# emonthKsm_1.net
KiCad netlist of a schematic drawn in EAGLE
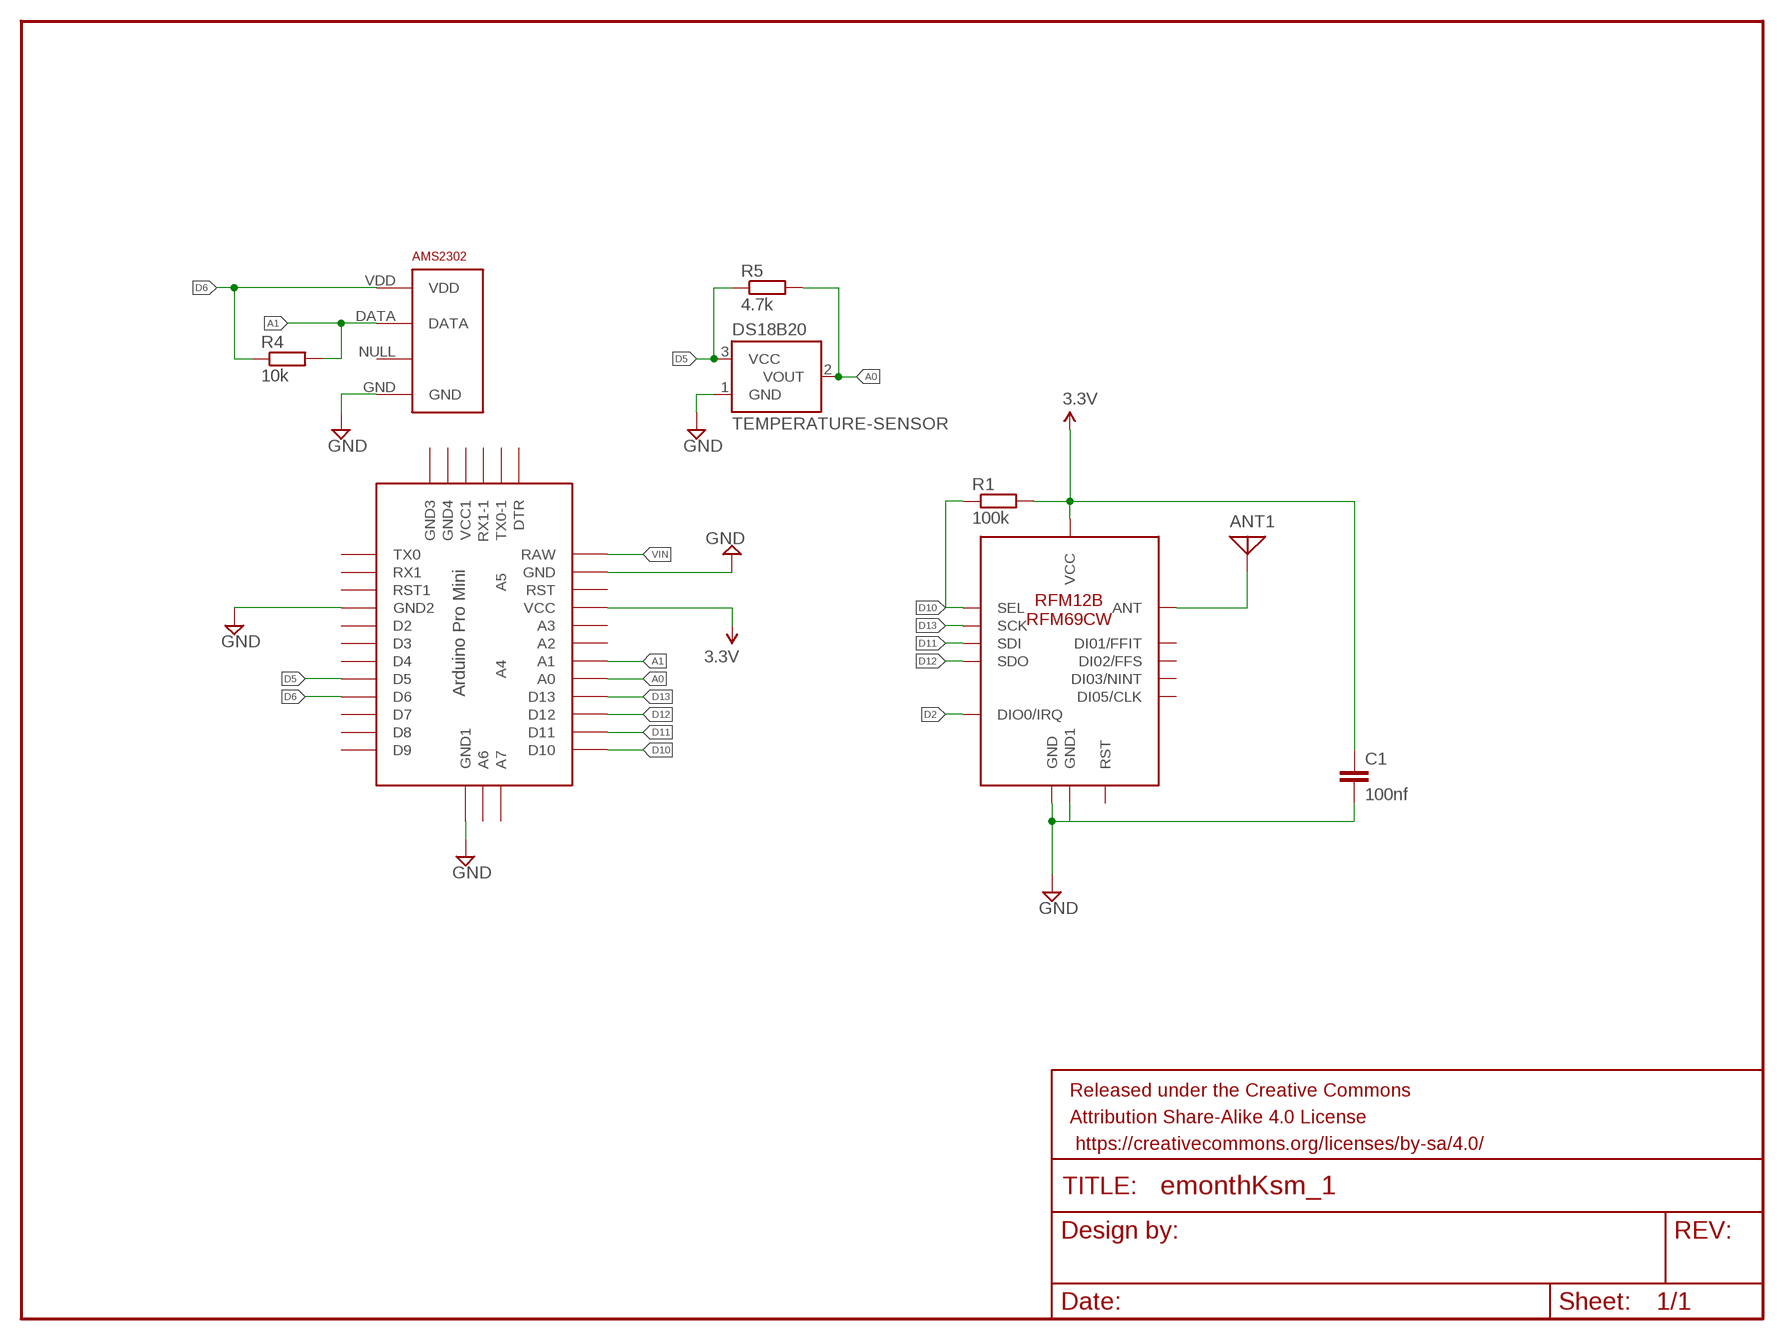
[diagram p0: schematic, sheet 1]

(export (version "E")
  (design (tool "Eeschema 10.0.6"))
  (components
    (comp (ref "AMS2302")
      (value "RHT03_DHT-22_AM2302")
      (footprint "eagle-import:RHT03_DHT-22")
      (libsource (lib "eagle-import") (part "RHT03_DHT-22_AM2302"))
    )
    (comp (ref "ANT1")
      (value "ANTENNA")
      (footprint "eagle-import:PAD-01")
      (libsource (lib "eagle-import") (part "ANTENNA"))
    )
    (comp (ref "ARDUINO")
      (value "ABK-PRO-MINI")
      (footprint "eagle-import:ABK-PRO-MINI")
      (libsource (lib "eagle-import") (part "ABK-PRO-MINI"))
    )
    (comp (ref "C1")
      (value "100nf")
      (footprint "eagle-import:C050-050X075")
      (libsource (lib "eagle-import") (part "C-EU050-050X075"))
    )
    (comp (ref "DS18B20")
      (value "TEMPERATURE-SENSOR")
      (footprint "eagle-import:TO-92")
      (libsource (lib "eagle-import") (part "TEMPERATURE-SENSOR"))
    )
    (comp (ref "FRAME1")
      (value "FRAME-LETTERNO_PACKAGE")
      (footprint "eagle-import:DUMMY")
      (fields (field (name "DESIGNER") "Nobody"))
      (libsource (lib "eagle-import") (part "FRAME-LETTERNO_PACKAGE"))
    )
    (comp (ref "R1")
      (value "100k")
      (footprint "eagle-import:0204_7")
      (libsource (lib "eagle-import") (part "R-EU_0204/7"))
    )
    (comp (ref "R4")
      (value "10k")
      (footprint "eagle-import:0204_7")
      (libsource (lib "eagle-import") (part "R-EU_0204/7"))
    )
    (comp (ref "R5")
      (value "4.7k")
      (footprint "eagle-import:0204_7")
      (libsource (lib "eagle-import") (part "R-EU_0204/7"))
    )
    (comp (ref "RFM69")
      (value "RFM12B/69CW")
      (footprint "eagle-import:RFM12B_69CW")
      (libsource (lib "eagle-import") (part "RFM12B/69CW"))
    )
  )
  (nets
    (net (code "1") (name "3.3V") (class "Default")
      (node (ref "ARDUINO") (pin "VCC") (pinfunction "VCC_VCC") (pintype "bidirectional"))
      (node (ref "C1") (pin "1") (pinfunction "1_1") (pintype "passive"))
      (node (ref "R1") (pin "2") (pinfunction "2_2") (pintype "passive"))
      (node (ref "RFM69") (pin "VDD") (pinfunction "VCC_VDD") (pintype "power_in"))
    )
    (net (code "2") (name "A0") (class "Default")
      (node (ref "ARDUINO") (pin "A0") (pinfunction "A0_A0") (pintype "bidirectional"))
      (node (ref "DS18B20") (pin "2") (pinfunction "VOUT_2") (pintype "bidirectional"))
      (node (ref "R5") (pin "2") (pinfunction "2_2") (pintype "passive"))
    )
    (net (code "3") (name "A1") (class "Default")
      (node (ref "AMS2302") (pin "DATA") (pinfunction "DATA_DATA") (pintype "bidirectional"))
      (node (ref "ARDUINO") (pin "A1") (pinfunction "A1_A1") (pintype "bidirectional"))
      (node (ref "R4") (pin "2") (pinfunction "2_2") (pintype "passive"))
    )
    (net (code "4") (name "D2") (class "Default")
      (node (ref "RFM69") (pin "IRQ") (pinfunction "DIO0/IRQ_IRQ") (pintype "open_collector"))
    )
    (net (code "5") (name "D5") (class "Default")
      (node (ref "ARDUINO") (pin "D5") (pinfunction "D5_D5") (pintype "bidirectional"))
      (node (ref "DS18B20") (pin "3") (pinfunction "VCC_3") (pintype "bidirectional"))
      (node (ref "R5") (pin "1") (pinfunction "1_1") (pintype "passive"))
    )
    (net (code "6") (name "D6") (class "Default")
      (node (ref "AMS2302") (pin "VDD") (pinfunction "VDD_VDD") (pintype "power_in"))
      (node (ref "ARDUINO") (pin "D6") (pinfunction "D6_D6") (pintype "bidirectional"))
      (node (ref "R4") (pin "1") (pinfunction "1_1") (pintype "passive"))
    )
    (net (code "7") (name "D10") (class "Default")
      (node (ref "ARDUINO") (pin "D10") (pinfunction "D10_D10") (pintype "bidirectional"))
      (node (ref "R1") (pin "1") (pinfunction "1_1") (pintype "passive"))
      (node (ref "RFM69") (pin "SEL") (pinfunction "SEL_SEL") (pintype "input"))
    )
    (net (code "8") (name "D11") (class "Default")
      (node (ref "ARDUINO") (pin "D11") (pinfunction "D11_D11") (pintype "bidirectional"))
      (node (ref "RFM69") (pin "SDI") (pinfunction "SDI_SDI") (pintype "input"))
    )
    (net (code "9") (name "D12") (class "Default")
      (node (ref "ARDUINO") (pin "D12") (pinfunction "D12_D12") (pintype "bidirectional"))
      (node (ref "RFM69") (pin "SDO") (pinfunction "SDO_SDO") (pintype "output"))
    )
    (net (code "10") (name "D13") (class "Default")
      (node (ref "ARDUINO") (pin "D13") (pinfunction "D13_D13") (pintype "bidirectional"))
      (node (ref "RFM69") (pin "SCK") (pinfunction "SCK_SCK") (pintype "input"))
    )
    (net (code "11") (name "GND") (class "Default")
      (node (ref "AMS2302") (pin "GND") (pinfunction "GND_GND") (pintype "power_in"))
      (node (ref "ARDUINO") (pin "GND") (pinfunction "GND_GND") (pintype "bidirectional"))
      (node (ref "ARDUINO") (pin "GND1") (pinfunction "GND2_GND1") (pintype "bidirectional"))
      (node (ref "ARDUINO") (pin "GND4") (pinfunction "GND1_GND4") (pintype "bidirectional"))
      (node (ref "C1") (pin "2") (pinfunction "2_2") (pintype "passive"))
      (node (ref "DS18B20") (pin "1") (pinfunction "GND_1") (pintype "bidirectional"))
      (node (ref "RFM69") (pin "GND") (pinfunction "GND_GND") (pintype "power_in"))
      (node (ref "RFM69") (pin "GND1") (pinfunction "GND1_GND1") (pintype "power_in"))
    )
    (net (code "12") (name "Net-(ANT1-Pad1)") (class "Default")
      (node (ref "ANT1") (pin "1") (pinfunction "1_1") (pintype "output"))
      (node (ref "RFM69") (pin "ANT") (pinfunction "ANT_ANT") (pintype "passive"))
    )
    (net (code "13") (name "VIN") (class "Default")
      (node (ref "ARDUINO") (pin "RAW") (pinfunction "RAW_RAW") (pintype "bidirectional"))
    )
    (net (code "14") (name "unconnected-(AMS2302-PadNULL)") (class "Default")
      (node (ref "AMS2302") (pin "NULL") (pinfunction "NULL_NULL") (pintype "no_connect"))
    )
    (net (code "15") (name "unconnected-(ARDUINO-GND3-PadGND2)") (class "Default")
      (node (ref "ARDUINO") (pin "GND2") (pinfunction "GND3_GND2") (pintype "bidirectional"))
    )
    (net (code "16") (name "unconnected-(ARDUINO-GND4-PadGND3)") (class "Default")
      (node (ref "ARDUINO") (pin "GND3") (pinfunction "GND4_GND3") (pintype "bidirectional"))
    )
    (net (code "17") (name "unconnected-(ARDUINO-PadA2)") (class "Default")
      (node (ref "ARDUINO") (pin "A2") (pinfunction "A2_A2") (pintype "bidirectional"))
    )
    (net (code "18") (name "unconnected-(ARDUINO-PadA3)") (class "Default")
      (node (ref "ARDUINO") (pin "A3") (pinfunction "A3_A3") (pintype "bidirectional"))
    )
    (net (code "19") (name "unconnected-(ARDUINO-PadA4)") (class "Default")
      (node (ref "ARDUINO") (pin "A4") (pinfunction "A4_A4") (pintype "bidirectional"))
    )
    (net (code "20") (name "unconnected-(ARDUINO-PadA5)") (class "Default")
      (node (ref "ARDUINO") (pin "A5") (pinfunction "A5_A5") (pintype "bidirectional"))
    )
    (net (code "21") (name "unconnected-(ARDUINO-PadA6)") (class "Default")
      (node (ref "ARDUINO") (pin "A6") (pinfunction "A6_A6") (pintype "bidirectional"))
    )
    (net (code "22") (name "unconnected-(ARDUINO-PadA7)") (class "Default")
      (node (ref "ARDUINO") (pin "A7") (pinfunction "A7_A7") (pintype "bidirectional"))
    )
    (net (code "23") (name "unconnected-(ARDUINO-PadD2)") (class "Default")
      (node (ref "ARDUINO") (pin "D2") (pinfunction "D2_D2") (pintype "bidirectional"))
    )
    (net (code "24") (name "unconnected-(ARDUINO-PadD3)") (class "Default")
      (node (ref "ARDUINO") (pin "D3") (pinfunction "D3_D3") (pintype "bidirectional"))
    )
    (net (code "25") (name "unconnected-(ARDUINO-PadD4)") (class "Default")
      (node (ref "ARDUINO") (pin "D4") (pinfunction "D4_D4") (pintype "bidirectional"))
    )
    (net (code "26") (name "unconnected-(ARDUINO-PadD7)") (class "Default")
      (node (ref "ARDUINO") (pin "D7") (pinfunction "D7_D7") (pintype "bidirectional"))
    )
    (net (code "27") (name "unconnected-(ARDUINO-PadD8)") (class "Default")
      (node (ref "ARDUINO") (pin "D8") (pinfunction "D8_D8") (pintype "bidirectional"))
    )
    (net (code "28") (name "unconnected-(ARDUINO-PadD9)") (class "Default")
      (node (ref "ARDUINO") (pin "D9") (pinfunction "D9_D9") (pintype "bidirectional"))
    )
    (net (code "29") (name "unconnected-(ARDUINO-PadDTR)") (class "Default")
      (node (ref "ARDUINO") (pin "DTR") (pinfunction "DTR_DTR") (pintype "bidirectional"))
    )
    (net (code "30") (name "unconnected-(ARDUINO-PadRST)") (class "Default")
      (node (ref "ARDUINO") (pin "RST") (pinfunction "RST_RST") (pintype "bidirectional"))
    )
    (net (code "31") (name "unconnected-(ARDUINO-PadRST1)") (class "Default")
      (node (ref "ARDUINO") (pin "RST1") (pinfunction "RST1_RST1") (pintype "bidirectional"))
    )
    (net (code "32") (name "unconnected-(ARDUINO-PadRX1)") (class "Default")
      (node (ref "ARDUINO") (pin "RX1") (pinfunction "RX1_RX1") (pintype "bidirectional"))
    )
    (net (code "33") (name "unconnected-(ARDUINO-PadRX1-1)") (class "Default")
      (node (ref "ARDUINO") (pin "RX1-1") (pinfunction "RX1-1_RX1-1") (pintype "bidirectional"))
    )
    (net (code "34") (name "unconnected-(ARDUINO-PadTX0)") (class "Default")
      (node (ref "ARDUINO") (pin "TX0") (pinfunction "TX0_TX0") (pintype "bidirectional"))
    )
    (net (code "35") (name "unconnected-(ARDUINO-PadTX0-1)") (class "Default")
      (node (ref "ARDUINO") (pin "TX0-1") (pinfunction "TX0-1_TX0-1") (pintype "bidirectional"))
    )
    (net (code "36") (name "unconnected-(ARDUINO-PadVCC1)") (class "Default")
      (node (ref "ARDUINO") (pin "VCC1") (pinfunction "VCC1_VCC1") (pintype "bidirectional"))
    )
    (net (code "37") (name "unconnected-(RFM69-DI01{slash}FFIT-PadFFIT)") (class "Default")
      (node (ref "RFM69") (pin "FFIT") (pinfunction "DI01/FFIT_FFIT") (pintype "passive"))
    )
    (net (code "38") (name "unconnected-(RFM69-DI02{slash}FFS-PadFFS)") (class "Default")
      (node (ref "RFM69") (pin "FFS") (pinfunction "DI02/FFS_FFS") (pintype "bidirectional"))
    )
    (net (code "39") (name "unconnected-(RFM69-DI03{slash}NINT-PadNINT)") (class "Default")
      (node (ref "RFM69") (pin "NINT") (pinfunction "DI03/NINT_NINT") (pintype "passive"))
    )
    (net (code "40") (name "unconnected-(RFM69-DI05{slash}CLK-PadCLK)") (class "Default")
      (node (ref "RFM69") (pin "CLK") (pinfunction "DI05/CLK_CLK") (pintype "passive"))
    )
    (net (code "41") (name "unconnected-(RFM69-PadRST)") (class "Default")
      (node (ref "RFM69") (pin "RST") (pinfunction "RST_RST") (pintype "open_collector"))
    )
  )
)
